# sensing_lab_shield_1-5-1.net
KiCad netlist of a schematic drawn in EAGLE
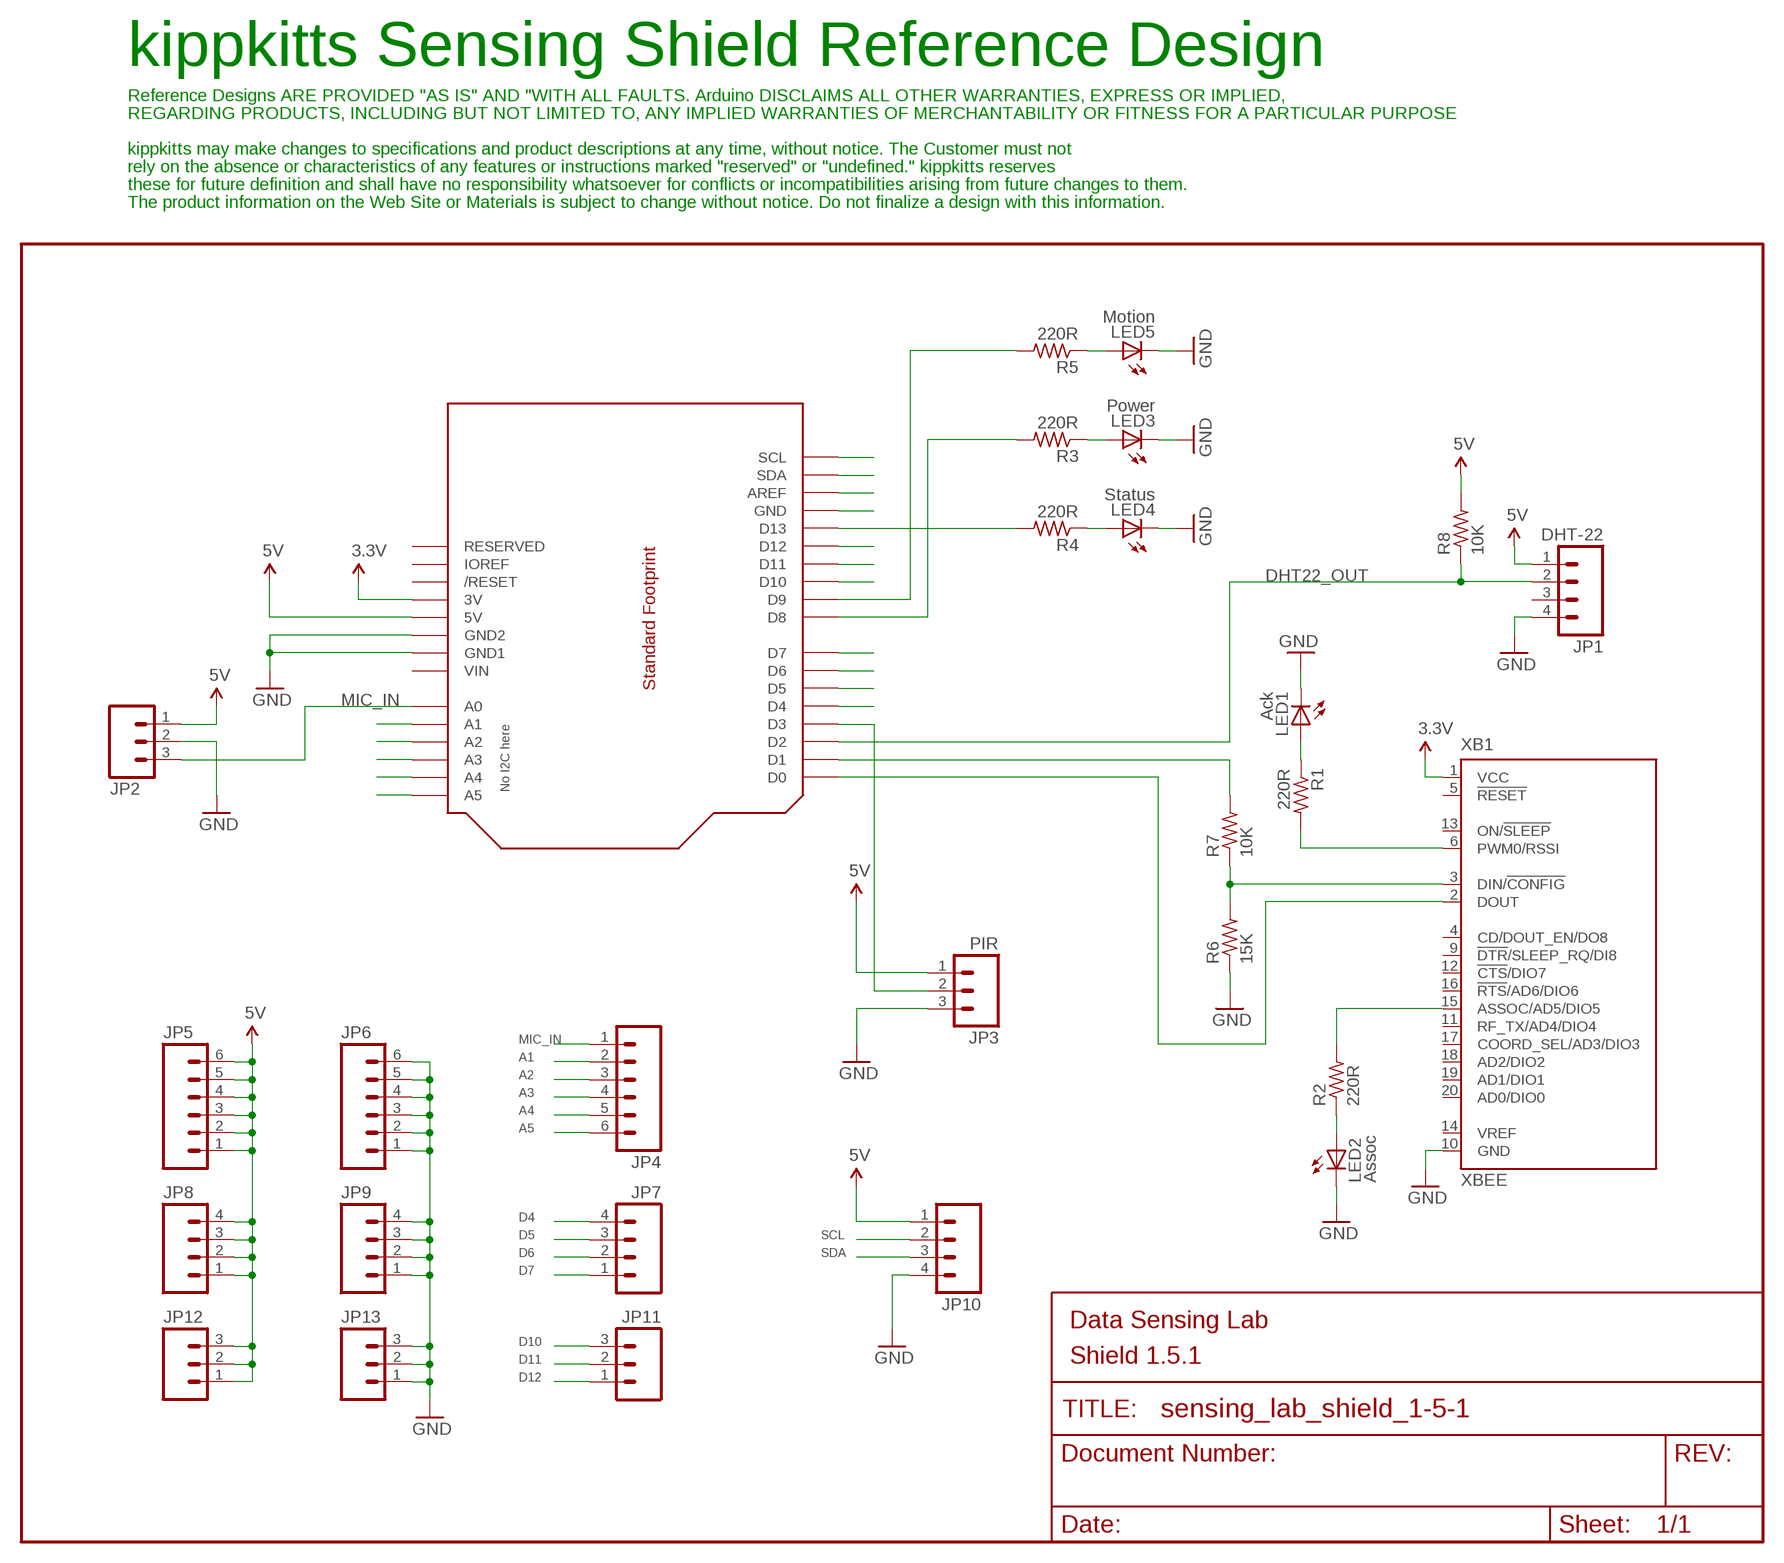
[diagram p0: schematic, sheet 1]

(export (version "E")
  (design (tool "Eeschema 10.0.6"))
  (components
    (comp (ref "JP1")
      (value "DHT-22")
      (footprint "eagle-import:1X04")
      (libsource (lib "eagle-import") (part "M04PTH"))
    )
    (comp (ref "JP2")
      (value "M03POLAR_LOCK")
      (footprint "eagle-import:MOLEX-1X3_LOCK")
      (libsource (lib "eagle-import") (part "M03POLAR_LOCK"))
    )
    (comp (ref "JP3")
      (value "PIR")
      (footprint "eagle-import:SCREWTERMINAL-3.5MM-3_LOCK.007S")
      (libsource (lib "eagle-import") (part "M03SCREW_LOCK"))
    )
    (comp (ref "JP4")
      (value "M06SIP")
      (footprint "eagle-import:1X06")
      (libsource (lib "eagle-import") (part "M06SIP"))
    )
    (comp (ref "JP5")
      (value "M06SIP")
      (footprint "eagle-import:1X06")
      (libsource (lib "eagle-import") (part "M06SIP"))
    )
    (comp (ref "JP6")
      (value "M06SIP")
      (footprint "eagle-import:1X06")
      (libsource (lib "eagle-import") (part "M06SIP"))
    )
    (comp (ref "JP7")
      (value "M04PTH")
      (footprint "eagle-import:1X04")
      (libsource (lib "eagle-import") (part "M04PTH"))
    )
    (comp (ref "JP8")
      (value "M04PTH")
      (footprint "eagle-import:1X04")
      (libsource (lib "eagle-import") (part "M04PTH"))
    )
    (comp (ref "JP9")
      (value "M04PTH")
      (footprint "eagle-import:1X04")
      (libsource (lib "eagle-import") (part "M04PTH"))
    )
    (comp (ref "JP10")
      (value "M04PTH")
      (footprint "eagle-import:1X04")
      (libsource (lib "eagle-import") (part "M04PTH"))
    )
    (comp (ref "JP11")
      (value "M03PTH")
      (footprint "eagle-import:1X03")
      (libsource (lib "eagle-import") (part "M03PTH"))
    )
    (comp (ref "JP12")
      (value "M03PTH")
      (footprint "eagle-import:1X03")
      (libsource (lib "eagle-import") (part "M03PTH"))
    )
    (comp (ref "JP13")
      (value "M03PTH")
      (footprint "eagle-import:1X03")
      (libsource (lib "eagle-import") (part "M03PTH"))
    )
    (comp (ref "LED1")
      (value "Ack")
      (footprint "eagle-import:LED3MM")
      (libsource (lib "eagle-import") (part "LED3MM"))
    )
    (comp (ref "LED2")
      (value "Assoc")
      (footprint "eagle-import:LED3MM")
      (libsource (lib "eagle-import") (part "LED3MM"))
    )
    (comp (ref "LED3")
      (value "Power")
      (footprint "eagle-import:LED3MM")
      (libsource (lib "eagle-import") (part "LED3MM"))
    )
    (comp (ref "LED4")
      (value "Status")
      (footprint "eagle-import:LED3MM")
      (libsource (lib "eagle-import") (part "LED3MM"))
    )
    (comp (ref "LED5")
      (value "Motion")
      (footprint "eagle-import:LED3MM")
      (libsource (lib "eagle-import") (part "LED3MM"))
    )
    (comp (ref "R1")
      (value "220R")
      (footprint "eagle-import:0207_10")
      (libsource (lib "eagle-import") (part "R-US_0207/10"))
    )
    (comp (ref "R2")
      (value "220R")
      (footprint "eagle-import:0207_10")
      (libsource (lib "eagle-import") (part "R-US_0207/10"))
    )
    (comp (ref "R3")
      (value "220R")
      (footprint "eagle-import:0207_10")
      (libsource (lib "eagle-import") (part "R-US_0207/10"))
    )
    (comp (ref "R4")
      (value "220R")
      (footprint "eagle-import:0207_10")
      (libsource (lib "eagle-import") (part "R-US_0207/10"))
    )
    (comp (ref "R5")
      (value "220R")
      (footprint "eagle-import:0207_10")
      (libsource (lib "eagle-import") (part "R-US_0207/10"))
    )
    (comp (ref "R6")
      (value "15K")
      (footprint "eagle-import:0207_10")
      (libsource (lib "eagle-import") (part "R-US_0207/10"))
    )
    (comp (ref "R7")
      (value "10K")
      (footprint "eagle-import:0207_10")
      (libsource (lib "eagle-import") (part "R-US_0207/10"))
    )
    (comp (ref "R8")
      (value "10K")
      (footprint "eagle-import:0207_10")
      (libsource (lib "eagle-import") (part "R-US_0207/10"))
    )
    (comp (ref "U1")
      (value "ARDUINOR3-DIMENSION")
      (footprint "eagle-import:ARDUINOR3")
      (libsource (lib "eagle-import") (part "ARDUINOR3-DIMENSION"))
    )
    (comp (ref "XB1")
      (value "XBEE")
      (footprint "eagle-import:XBEE")
      (fields (field (name "MPN") "XBP24-Z7UIT-004"))
      (libsource (lib "eagle-import") (part "XBEE"))
    )
  )
  (nets
    (net (code "1") (name "/A1") (class "Default")
      (node (ref "JP4") (pin "2") (pinfunction "2_2") (pintype "passive"))
      (node (ref "U1") (pin "A1") (pinfunction "A1_A1") (pintype "bidirectional"))
    )
    (net (code "2") (name "/A2") (class "Default")
      (node (ref "JP4") (pin "3") (pinfunction "3_3") (pintype "passive"))
      (node (ref "U1") (pin "A2") (pinfunction "A2_A2") (pintype "bidirectional"))
    )
    (net (code "3") (name "/A3") (class "Default")
      (node (ref "JP4") (pin "4") (pinfunction "4_4") (pintype "passive"))
      (node (ref "U1") (pin "A3") (pinfunction "A3_A3") (pintype "bidirectional"))
    )
    (net (code "4") (name "/A4") (class "Default")
      (node (ref "JP4") (pin "5") (pinfunction "5_5") (pintype "passive"))
      (node (ref "U1") (pin "A4") (pinfunction "A4_A4") (pintype "bidirectional"))
    )
    (net (code "5") (name "/A5") (class "Default")
      (node (ref "JP4") (pin "6") (pinfunction "6_6") (pintype "passive"))
      (node (ref "U1") (pin "A5") (pinfunction "A5_A5") (pintype "bidirectional"))
    )
    (net (code "6") (name "/D4") (class "Default")
      (node (ref "JP7") (pin "4") (pinfunction "4_4") (pintype "passive"))
      (node (ref "U1") (pin "D4") (pinfunction "D4_D4") (pintype "bidirectional"))
    )
    (net (code "7") (name "/D5") (class "Default")
      (node (ref "JP7") (pin "3") (pinfunction "3_3") (pintype "passive"))
      (node (ref "U1") (pin "D5") (pinfunction "D5_D5") (pintype "bidirectional"))
    )
    (net (code "8") (name "/D6") (class "Default")
      (node (ref "JP7") (pin "2") (pinfunction "2_2") (pintype "passive"))
      (node (ref "U1") (pin "D6") (pinfunction "D6_D6") (pintype "bidirectional"))
    )
    (net (code "9") (name "/D7") (class "Default")
      (node (ref "JP7") (pin "1") (pinfunction "1_1") (pintype "passive"))
      (node (ref "U1") (pin "D7") (pinfunction "D7_D7") (pintype "bidirectional"))
    )
    (net (code "10") (name "/D10") (class "Default")
      (node (ref "JP11") (pin "3") (pinfunction "3_3") (pintype "passive"))
      (node (ref "U1") (pin "D10") (pinfunction "D10_D10") (pintype "bidirectional"))
    )
    (net (code "11") (name "/D11") (class "Default")
      (node (ref "JP11") (pin "2") (pinfunction "2_2") (pintype "passive"))
      (node (ref "U1") (pin "D11") (pinfunction "D11_D11") (pintype "bidirectional"))
    )
    (net (code "12") (name "/D12") (class "Default")
      (node (ref "JP11") (pin "1") (pinfunction "1_1") (pintype "passive"))
      (node (ref "U1") (pin "D12") (pinfunction "D12_D12") (pintype "bidirectional"))
    )
    (net (code "13") (name "/DHT22_OUT") (class "Default")
      (node (ref "JP1") (pin "2") (pinfunction "2_2") (pintype "passive"))
      (node (ref "R8") (pin "1") (pinfunction "1_1") (pintype "passive"))
      (node (ref "U1") (pin "D2") (pinfunction "D2_D2") (pintype "bidirectional"))
    )
    (net (code "14") (name "/MIC_IN") (class "Default")
      (node (ref "JP2") (pin "3") (pinfunction "3_3") (pintype "passive"))
      (node (ref "JP4") (pin "1") (pinfunction "1_1") (pintype "passive"))
      (node (ref "U1") (pin "A0") (pinfunction "A0_A0") (pintype "bidirectional"))
    )
    (net (code "15") (name "/SCL") (class "Default")
      (node (ref "JP10") (pin "2") (pinfunction "2_2") (pintype "passive"))
      (node (ref "U1") (pin "SCL") (pinfunction "SCL_SCL") (pintype "bidirectional"))
    )
    (net (code "16") (name "/SDA") (class "Default")
      (node (ref "JP10") (pin "3") (pinfunction "3_3") (pintype "passive"))
      (node (ref "U1") (pin "SDA") (pinfunction "SDA_SDA") (pintype "bidirectional"))
    )
    (net (code "17") (name "/VIN") (class "Default")
      (node (ref "U1") (pin "VIN") (pinfunction "VIN_VIN") (pintype "power_in"))
    )
    (net (code "18") (name "3.3V") (class "Default")
      (node (ref "U1") (pin "3V") (pinfunction "3V_3V") (pintype "power_in"))
      (node (ref "XB1") (pin "1") (pinfunction "VCC_1") (pintype "power_in"))
    )
    (net (code "19") (name "5V") (class "Default")
      (node (ref "JP1") (pin "1") (pinfunction "1_1") (pintype "passive"))
      (node (ref "JP10") (pin "1") (pinfunction "1_1") (pintype "passive"))
      (node (ref "JP12") (pin "1") (pinfunction "1_1") (pintype "passive"))
      (node (ref "JP12") (pin "2") (pinfunction "2_2") (pintype "passive"))
      (node (ref "JP12") (pin "3") (pinfunction "3_3") (pintype "passive"))
      (node (ref "JP2") (pin "1") (pinfunction "1_1") (pintype "passive"))
      (node (ref "JP3") (pin "1") (pinfunction "1_1") (pintype "passive"))
      (node (ref "JP5") (pin "1") (pinfunction "1_1") (pintype "passive"))
      (node (ref "JP5") (pin "2") (pinfunction "2_2") (pintype "passive"))
      (node (ref "JP5") (pin "3") (pinfunction "3_3") (pintype "passive"))
      (node (ref "JP5") (pin "4") (pinfunction "4_4") (pintype "passive"))
      (node (ref "JP5") (pin "5") (pinfunction "5_5") (pintype "passive"))
      (node (ref "JP5") (pin "6") (pinfunction "6_6") (pintype "passive"))
      (node (ref "JP8") (pin "1") (pinfunction "1_1") (pintype "passive"))
      (node (ref "JP8") (pin "2") (pinfunction "2_2") (pintype "passive"))
      (node (ref "JP8") (pin "3") (pinfunction "3_3") (pintype "passive"))
      (node (ref "JP8") (pin "4") (pinfunction "4_4") (pintype "passive"))
      (node (ref "R8") (pin "2") (pinfunction "2_2") (pintype "passive"))
      (node (ref "U1") (pin "5V") (pinfunction "5V_5V") (pintype "power_in"))
    )
    (net (code "20") (name "GND") (class "Default")
      (node (ref "JP1") (pin "4") (pinfunction "4_4") (pintype "passive"))
      (node (ref "JP10") (pin "4") (pinfunction "4_4") (pintype "passive"))
      (node (ref "JP13") (pin "1") (pinfunction "1_1") (pintype "passive"))
      (node (ref "JP13") (pin "2") (pinfunction "2_2") (pintype "passive"))
      (node (ref "JP13") (pin "3") (pinfunction "3_3") (pintype "passive"))
      (node (ref "JP2") (pin "2") (pinfunction "2_2") (pintype "passive"))
      (node (ref "JP3") (pin "3") (pinfunction "3_3") (pintype "passive"))
      (node (ref "JP6") (pin "1") (pinfunction "1_1") (pintype "passive"))
      (node (ref "JP6") (pin "2") (pinfunction "2_2") (pintype "passive"))
      (node (ref "JP6") (pin "3") (pinfunction "3_3") (pintype "passive"))
      (node (ref "JP6") (pin "4") (pinfunction "4_4") (pintype "passive"))
      (node (ref "JP6") (pin "5") (pinfunction "5_5") (pintype "passive"))
      (node (ref "JP6") (pin "6") (pinfunction "6_6") (pintype "passive"))
      (node (ref "JP9") (pin "1") (pinfunction "1_1") (pintype "passive"))
      (node (ref "JP9") (pin "2") (pinfunction "2_2") (pintype "passive"))
      (node (ref "JP9") (pin "3") (pinfunction "3_3") (pintype "passive"))
      (node (ref "JP9") (pin "4") (pinfunction "4_4") (pintype "passive"))
      (node (ref "LED1") (pin "K") (pinfunction "C_K") (pintype "passive"))
      (node (ref "LED2") (pin "K") (pinfunction "C_K") (pintype "passive"))
      (node (ref "LED3") (pin "K") (pinfunction "C_K") (pintype "passive"))
      (node (ref "LED4") (pin "K") (pinfunction "C_K") (pintype "passive"))
      (node (ref "LED5") (pin "K") (pinfunction "C_K") (pintype "passive"))
      (node (ref "R6") (pin "1") (pinfunction "1_1") (pintype "passive"))
      (node (ref "U1") (pin "GND1") (pinfunction "GND1_GND1") (pintype "power_in"))
      (node (ref "U1") (pin "GND2") (pinfunction "GND2_GND2") (pintype "power_in"))
      (node (ref "XB1") (pin "10") (pinfunction "GND_10") (pintype "power_in"))
    )
    (net (code "21") (name "Net-(JP3-Pad2)") (class "Default")
      (node (ref "JP3") (pin "2") (pinfunction "2_2") (pintype "passive"))
      (node (ref "U1") (pin "D3") (pinfunction "D3_D3") (pintype "bidirectional"))
    )
    (net (code "22") (name "Net-(LED1-PadA)") (class "Default")
      (node (ref "LED1") (pin "A") (pinfunction "A_A") (pintype "passive"))
      (node (ref "R1") (pin "1") (pinfunction "1_1") (pintype "passive"))
    )
    (net (code "23") (name "Net-(LED2-PadA)") (class "Default")
      (node (ref "LED2") (pin "A") (pinfunction "A_A") (pintype "passive"))
      (node (ref "R2") (pin "1") (pinfunction "1_1") (pintype "passive"))
    )
    (net (code "24") (name "Net-(LED3-PadA)") (class "Default")
      (node (ref "LED3") (pin "A") (pinfunction "A_A") (pintype "passive"))
      (node (ref "R3") (pin "1") (pinfunction "1_1") (pintype "passive"))
    )
    (net (code "25") (name "Net-(LED4-PadA)") (class "Default")
      (node (ref "LED4") (pin "A") (pinfunction "A_A") (pintype "passive"))
      (node (ref "R4") (pin "1") (pinfunction "1_1") (pintype "passive"))
    )
    (net (code "26") (name "Net-(LED5-PadA)") (class "Default")
      (node (ref "LED5") (pin "A") (pinfunction "A_A") (pintype "passive"))
      (node (ref "R5") (pin "1") (pinfunction "1_1") (pintype "passive"))
    )
    (net (code "27") (name "Net-(R3-Pad2)") (class "Default")
      (node (ref "R3") (pin "2") (pinfunction "2_2") (pintype "passive"))
      (node (ref "U1") (pin "D8") (pinfunction "D8_D8") (pintype "bidirectional"))
    )
    (net (code "28") (name "Net-(R4-Pad2)") (class "Default")
      (node (ref "R4") (pin "2") (pinfunction "2_2") (pintype "passive"))
      (node (ref "U1") (pin "D13") (pinfunction "D13_D13") (pintype "bidirectional"))
    )
    (net (code "29") (name "Net-(R5-Pad2)") (class "Default")
      (node (ref "R5") (pin "2") (pinfunction "2_2") (pintype "passive"))
      (node (ref "U1") (pin "D9") (pinfunction "D9_D9") (pintype "bidirectional"))
    )
    (net (code "30") (name "Net-(R7-Pad2)") (class "Default")
      (node (ref "R7") (pin "2") (pinfunction "2_2") (pintype "passive"))
      (node (ref "U1") (pin "D1") (pinfunction "D1_D1") (pintype "bidirectional"))
    )
    (net (code "31") (name "Net-(XB1-ASSOC{slash}AD5{slash}DIO5)") (class "Default")
      (node (ref "R2") (pin "2") (pinfunction "2_2") (pintype "passive"))
      (node (ref "XB1") (pin "15") (pinfunction "ASSOC/AD5/DIO5_15") (pintype "bidirectional"))
    )
    (net (code "32") (name "Net-(XB1-DIN{slash}~{CONFIG})") (class "Default")
      (node (ref "R6") (pin "2") (pinfunction "2_2") (pintype "passive"))
      (node (ref "R7") (pin "1") (pinfunction "1_1") (pintype "passive"))
      (node (ref "XB1") (pin "3") (pinfunction "DIN/~{CONFIG}_3") (pintype "input"))
    )
    (net (code "33") (name "Net-(XB1-DOUT)") (class "Default")
      (node (ref "U1") (pin "D0") (pinfunction "D0_D0") (pintype "bidirectional"))
      (node (ref "XB1") (pin "2") (pinfunction "DOUT_2") (pintype "output"))
    )
    (net (code "34") (name "Net-(XB1-PWM0{slash}RSSI)") (class "Default")
      (node (ref "R1") (pin "2") (pinfunction "2_2") (pintype "passive"))
      (node (ref "XB1") (pin "6") (pinfunction "PWM0/RSSI_6") (pintype "output"))
    )
    (net (code "35") (name "unconnected-(JP1-Pad3)") (class "Default")
      (node (ref "JP1") (pin "3") (pinfunction "3_3") (pintype "passive"))
    )
    (net (code "36") (name "unconnected-(U1-PadAREF)") (class "Default")
      (node (ref "U1") (pin "AREF") (pinfunction "AREF_AREF") (pintype "bidirectional"))
    )
    (net (code "37") (name "unconnected-(U1-PadGND)") (class "Default")
      (node (ref "U1") (pin "GND") (pinfunction "GND_GND") (pintype "power_in"))
    )
    (net (code "38") (name "unconnected-(U1-PadIOREF)") (class "Default")
      (node (ref "U1") (pin "IOREF") (pinfunction "IOREF_IOREF") (pintype "output"))
    )
    (net (code "39") (name "unconnected-(U1-PadRESERVED)") (class "Default")
      (node (ref "U1") (pin "RESERVED") (pinfunction "RESERVED_RESERVED") (pintype "no_connect"))
    )
    (net (code "40") (name "unconnected-(U1-{slash}RESET-PadRESET)") (class "Default")
      (node (ref "U1") (pin "RESET") (pinfunction "/RESET_RESET") (pintype "bidirectional"))
    )
    (net (code "41") (name "unconnected-(XB1-AD0{slash}DIO0-Pad20)") (class "Default")
      (node (ref "XB1") (pin "20") (pinfunction "AD0/DIO0_20") (pintype "bidirectional"))
    )
    (net (code "42") (name "unconnected-(XB1-AD1{slash}DIO1-Pad19)") (class "Default")
      (node (ref "XB1") (pin "19") (pinfunction "AD1/DIO1_19") (pintype "bidirectional"))
    )
    (net (code "43") (name "unconnected-(XB1-AD2{slash}DIO2-Pad18)") (class "Default")
      (node (ref "XB1") (pin "18") (pinfunction "AD2/DIO2_18") (pintype "bidirectional"))
    )
    (net (code "44") (name "unconnected-(XB1-CD{slash}DOUT_EN{slash}DO8-Pad4)") (class "Default")
      (node (ref "XB1") (pin "4") (pinfunction "CD/DOUT_EN/DO8_4") (pintype "output"))
    )
    (net (code "45") (name "unconnected-(XB1-COORD_SEL{slash}AD3{slash}DIO3-Pad17)") (class "Default")
      (node (ref "XB1") (pin "17") (pinfunction "COORD_SEL/AD3/DIO3_17") (pintype "bidirectional"))
    )
    (net (code "46") (name "unconnected-(XB1-ON{slash}~{SLEEP}-Pad13)") (class "Default")
      (node (ref "XB1") (pin "13") (pinfunction "ON/~{SLEEP}_13") (pintype "output"))
    )
    (net (code "47") (name "unconnected-(XB1-RF_TX{slash}AD4{slash}DIO4-Pad11)") (class "Default")
      (node (ref "XB1") (pin "11") (pinfunction "RF_TX/AD4/DIO4_11") (pintype "bidirectional"))
    )
    (net (code "48") (name "unconnected-(XB1-VREF-Pad14)") (class "Default")
      (node (ref "XB1") (pin "14") (pinfunction "VREF_14") (pintype "input"))
    )
    (net (code "49") (name "unconnected-(XB1-~{CTS}{slash}DIO7-Pad12)") (class "Default")
      (node (ref "XB1") (pin "12") (pinfunction "~{CTS}/DIO7_12") (pintype "bidirectional"))
    )
    (net (code "50") (name "unconnected-(XB1-~{DTR}{slash}SLEEP_RQ{slash}DI8-Pad9)") (class "Default")
      (node (ref "XB1") (pin "9") (pinfunction "~{DTR}/SLEEP_RQ/DI8_9") (pintype "bidirectional"))
    )
    (net (code "51") (name "unconnected-(XB1-~{RESET}-Pad5)") (class "Default")
      (node (ref "XB1") (pin "5") (pinfunction "~{RESET}_5") (pintype "input"))
    )
    (net (code "52") (name "unconnected-(XB1-~{RTS}{slash}AD6{slash}DIO6-Pad16)") (class "Default")
      (node (ref "XB1") (pin "16") (pinfunction "~{RTS}/AD6/DIO6_16") (pintype "bidirectional"))
    )
  )
)
